# 2002_Pile-Accu.net
KiCad netlist of a schematic drawn in Altium Designer
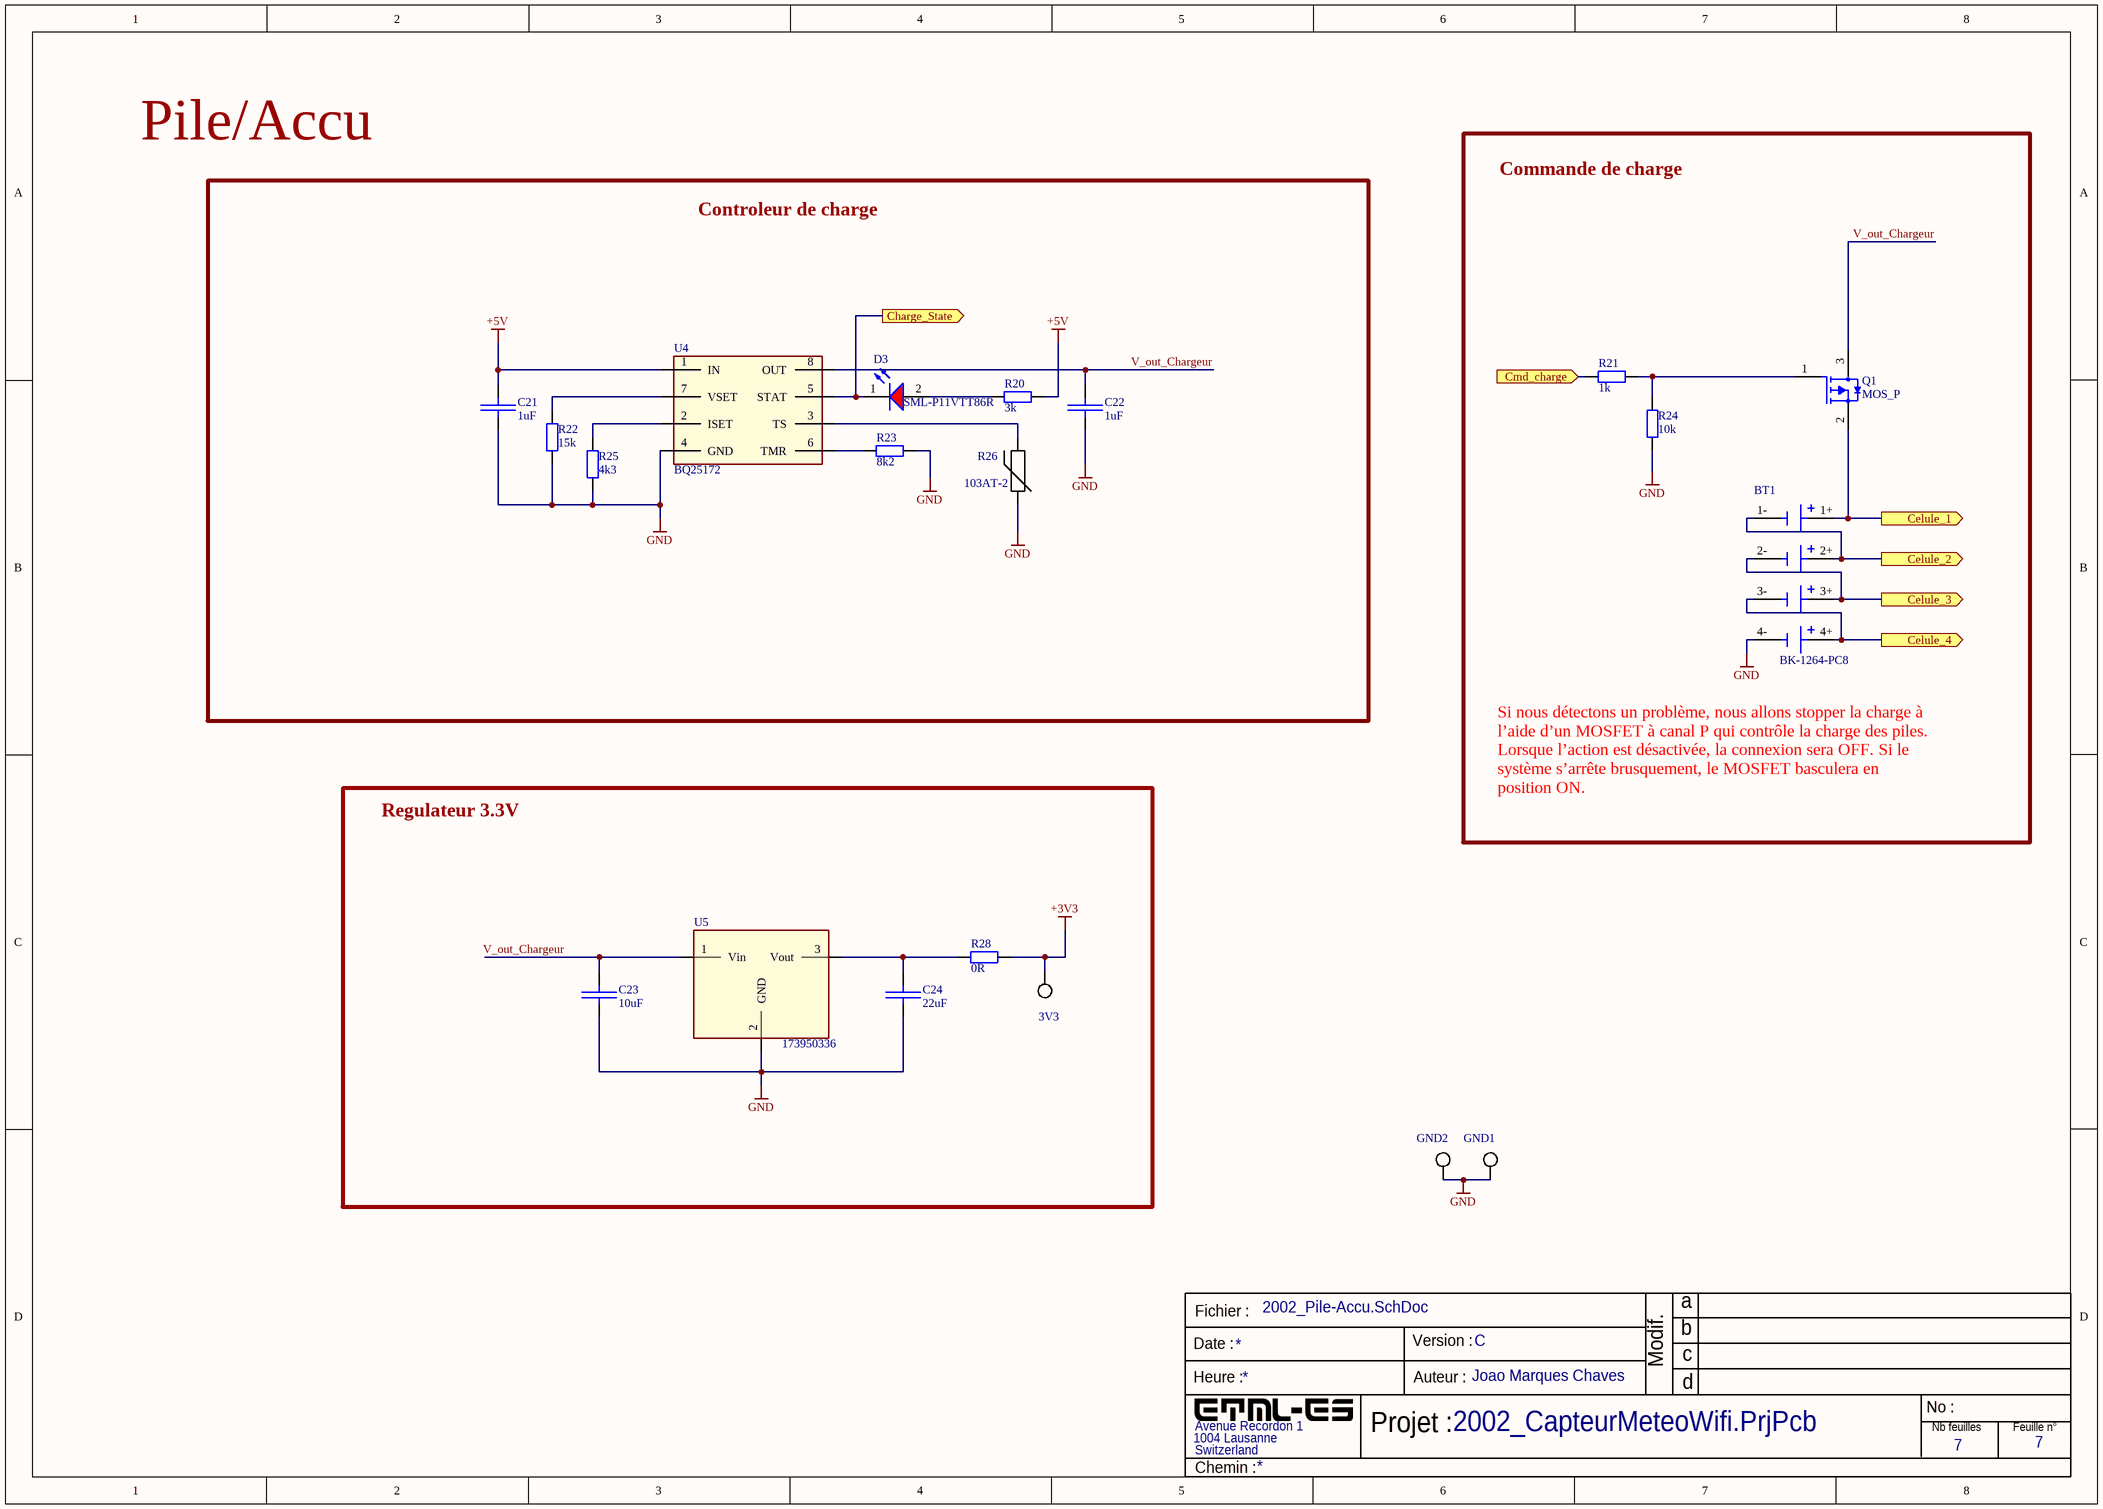
[diagram p0: 2002_Pile-Accu.SchDoc]

(export (version "E")
  (design (tool "Eeschema 10.0.6"))
  (components
    (comp (ref "3V3")
      (value "5019")
      (footprint "TESTPOINT_SMD")
      (description "Test point smd")
      (libsource (lib "2002_CapteurMeteoWifi") (part "TESTPOINT"))
    )
    (comp (ref "BT1")
      (value "BK-1264-PC8")
      (footprint "BAT_BK-1264-PC8")
      (description "Battery Holder (Open) AAA 4 Cell PC Pin")
      (libsource (lib "Schlib1") (part "BK-1264-PC8"))
    )
    (comp (ref "C21")
      (value "1uF")
      (footprint "0805")
      (description "Capacitor smd")
      (libsource (lib "2002_CapteurMeteoWifi") (part "Condensator"))
    )
    (comp (ref "C22")
      (value "1uF")
      (footprint "0805")
      (description "Capacitor smd")
      (libsource (lib "2002_CapteurMeteoWifi") (part "Condensator"))
    )
    (comp (ref "C23")
      (value "10uF")
      (footprint "0805")
      (description "Capacitor smd")
      (libsource (lib "2002_CapteurMeteoWifi") (part "Condensator"))
    )
    (comp (ref "C24")
      (value "22uF")
      (footprint "0805")
      (description "Capacitor smd")
      (libsource (lib "2002_CapteurMeteoWifi") (part "Condensator"))
    )
    (comp (ref "D3")
      (value "SML-P11VTT86R")
      (footprint "LED_SML-P11VTT86R")
      (description "WL-SMCW Mono-color Chip LED Waterclear, size 0805, Super Red, 1.9V, 140°")
      (fields
        (field (name "MANUFACTURER PART NUMBER") "150080SS75000")
        (field (name "MANUFACTURER") "Wurth Elektronik")
      )
      (libsource (lib "WL-SMCW") (part "150080SS75000"))
    )
    (comp (ref "GND1")
      (value "5019")
      (footprint "TESTPOINT_SMD")
      (description "Test point smd")
      (libsource (lib "2002_CapteurMeteoWifi") (part "TESTPOINT"))
    )
    (comp (ref "GND2")
      (value "5019")
      (footprint "TESTPOINT_SMD")
      (description "Test point smd")
      (libsource (lib "2002_CapteurMeteoWifi") (part "TESTPOINT"))
    )
    (comp (ref "Q1") (value "MOS_P") (footprint "SI5618-TP") (libsource (lib "Schlib1") (part "MOS_P")))
    (comp (ref "R20")
      (value "3k")
      (footprint "0805")
      (description "Resistor smd")
      (fields (field (name "Comment") "3k2") (field (name "PUBLISHER") "Altium Limited"))
      (libsource (lib "") (part "Res2_1_1"))
    )
    (comp (ref "R21")
      (value "1k")
      (footprint "0805")
      (description "Resistor smd")
      (fields (field (name "PUBLISHER") "Altium Limited"))
      (libsource (lib "2209_CommandeDomotiqueIR_1") (part "Res2"))
    )
    (comp (ref "R22")
      (value "15k")
      (footprint "0805")
      (description "Resistor smd")
      (fields (field (name "PUBLISHER") "Altium Limited"))
      (libsource (lib "2209_CommandeDomotiqueIR_1") (part "Res2_1"))
    )
    (comp (ref "R23")
      (value "8k2")
      (footprint "0805")
      (description "Resistor smd")
      (fields (field (name "PUBLISHER") "Altium Limited"))
      (libsource (lib "") (part "Res2_1_1"))
    )
    (comp (ref "R24")
      (value "10k")
      (footprint "0805")
      (description "Resistor smd")
      (fields (field (name "PUBLISHER") "Altium Limited"))
      (libsource (lib "2209_CommandeDomotiqueIR_1") (part "Res2_1"))
    )
    (comp (ref "R25")
      (value "4k3")
      (footprint "0805")
      (description "Resistor smd")
      (fields (field (name "PUBLISHER") "Altium Limited"))
      (libsource (lib "2209_CommandeDomotiqueIR_1") (part "Res2_1"))
    )
    (comp (ref "R26")
      (value "103AT-2")
      (footprint "103AT51PFT")
      (description "thermistor")
      (libsource (lib "Schlib1") (part "103AT-2"))
    )
    (comp (ref "R28")
      (value "0R")
      (footprint "0805")
      (description "Resistor smd")
      (fields (field (name "PUBLISHER") "Altium Limited"))
      (libsource (lib "") (part "Res2_1_1"))
    )
    (comp (ref "U4")
      (value "BQ25172")
      (footprint "BQ25172DSGR")
      (description "Linear Battery Charger for 1- to 6-Cell NiMH Batteries")
      (libsource (lib "Schlib1") (part "BQ25172"))
    )
    (comp (ref "U5")
      (value "173950336")
      (footprint "173950336")
      (description "DC DC CONVERTER 3.3V")
      (libsource (lib "Schlib1") (part "173950336"))
    )
  )
  (nets
    (net (code "1") (name "+3V3") (class "Default")
      (node (ref "3V3") (pin "1") (pinfunction "1_1") (pintype "passive"))
      (node (ref "R28") (pin "1") (pinfunction "1_1") (pintype "passive"))
    )
    (net (code "2") (name "+5V") (class "Default")
      (node (ref "C21") (pin "1") (pinfunction "1_1") (pintype "passive"))
      (node (ref "R20") (pin "1") (pinfunction "1_1") (pintype "passive"))
      (node (ref "U4") (pin "1") (pinfunction "IN_1") (pintype "passive"))
    )
    (net (code "3") (name "/Celule_1") (class "Default")
      (node (ref "BT1") (pin "1+") (pinfunction "1+_1+") (pintype "passive"))
      (node (ref "Q1") (pin "2") (pinfunction "S_2") (pintype "passive"))
    )
    (net (code "4") (name "/Celule_2") (class "Default")
      (node (ref "BT1") (pin "1-") (pinfunction "1-_1-") (pintype "passive"))
      (node (ref "BT1") (pin "2+") (pinfunction "2+_2+") (pintype "passive"))
    )
    (net (code "5") (name "/Celule_3") (class "Default")
      (node (ref "BT1") (pin "2-") (pinfunction "2-_2-") (pintype "passive"))
      (node (ref "BT1") (pin "3+") (pinfunction "3+_3+") (pintype "passive"))
    )
    (net (code "6") (name "/Celule_4") (class "Default")
      (node (ref "BT1") (pin "3-") (pinfunction "3-_3-") (pintype "passive"))
      (node (ref "BT1") (pin "4+") (pinfunction "4+_4+") (pintype "passive"))
    )
    (net (code "7") (name "/Charge_State") (class "Default")
      (node (ref "D3") (pin "1") (pinfunction "K_1") (pintype "passive"))
      (node (ref "U4") (pin "5") (pinfunction "STAT_5") (pintype "passive"))
    )
    (net (code "8") (name "/Cmd_charge") (class "Default")
      (node (ref "R21") (pin "2") (pinfunction "2_2") (pintype "passive"))
    )
    (net (code "9") (name "/V_out_Chargeur") (class "Default")
      (node (ref "C22") (pin "1") (pinfunction "1_1") (pintype "passive"))
      (node (ref "C23") (pin "1") (pinfunction "1_1") (pintype "passive"))
      (node (ref "Q1") (pin "3") (pinfunction "D_3") (pintype "passive"))
      (node (ref "U4") (pin "8") (pinfunction "OUT_8") (pintype "passive"))
      (node (ref "U5") (pin "1") (pinfunction "Vin_1") (pintype "passive"))
    )
    (net (code "10") (name "GND") (class "Default")
      (node (ref "BT1") (pin "4-") (pinfunction "4-_4-") (pintype "passive"))
      (node (ref "C21") (pin "2") (pinfunction "2_2") (pintype "passive"))
      (node (ref "C22") (pin "2") (pinfunction "2_2") (pintype "passive"))
      (node (ref "C23") (pin "2") (pinfunction "2_2") (pintype "passive"))
      (node (ref "C24") (pin "2") (pinfunction "2_2") (pintype "passive"))
      (node (ref "GND1") (pin "1") (pinfunction "1_1") (pintype "passive"))
      (node (ref "GND2") (pin "1") (pinfunction "1_1") (pintype "passive"))
      (node (ref "R22") (pin "1") (pinfunction "1_1") (pintype "passive"))
      (node (ref "R23") (pin "1") (pinfunction "1_1") (pintype "passive"))
      (node (ref "R24") (pin "1") (pinfunction "1_1") (pintype "passive"))
      (node (ref "R25") (pin "1") (pinfunction "1_1") (pintype "passive"))
      (node (ref "R26") (pin "2") (pinfunction "0_2") (pintype "passive"))
      (node (ref "U4") (pin "4") (pinfunction "GND_4") (pintype "passive"))
      (node (ref "U5") (pin "2") (pinfunction "GND_2") (pintype "passive"))
    )
    (net (code "11") (name "Net-(D3-A)") (class "Default")
      (node (ref "D3") (pin "2") (pinfunction "A_2") (pintype "passive"))
      (node (ref "R20") (pin "2") (pinfunction "2_2") (pintype "passive"))
    )
    (net (code "12") (name "Net-(Q1-G)") (class "Default")
      (node (ref "Q1") (pin "1") (pinfunction "G_1") (pintype "passive"))
      (node (ref "R21") (pin "1") (pinfunction "1_1") (pintype "passive"))
      (node (ref "R24") (pin "2") (pinfunction "2_2") (pintype "passive"))
    )
    (net (code "13") (name "Net-(U4-ISET)") (class "Default")
      (node (ref "R25") (pin "2") (pinfunction "2_2") (pintype "passive"))
      (node (ref "U4") (pin "2") (pinfunction "ISET_2") (pintype "passive"))
    )
    (net (code "14") (name "Net-(U4-TMR)") (class "Default")
      (node (ref "R23") (pin "2") (pinfunction "2_2") (pintype "passive"))
      (node (ref "U4") (pin "6") (pinfunction "TMR_6") (pintype "passive"))
    )
    (net (code "15") (name "Net-(U4-TS)") (class "Default")
      (node (ref "R26") (pin "1") (pinfunction "0_1") (pintype "passive"))
      (node (ref "U4") (pin "3") (pinfunction "TS_3") (pintype "passive"))
    )
    (net (code "16") (name "Net-(U4-VSET)") (class "Default")
      (node (ref "R22") (pin "2") (pinfunction "2_2") (pintype "passive"))
      (node (ref "U4") (pin "7") (pinfunction "VSET_7") (pintype "passive"))
    )
    (net (code "17") (name "Net-(U5-Vout)") (class "Default")
      (node (ref "C24") (pin "1") (pinfunction "1_1") (pintype "passive"))
      (node (ref "R28") (pin "2") (pinfunction "2_2") (pintype "passive"))
      (node (ref "U5") (pin "3") (pinfunction "Vout_3") (pintype "passive"))
    )
  )
)
